# PFC_Method_AirSens_V1.net
KiCad netlist of a schematic drawn in EAGLE
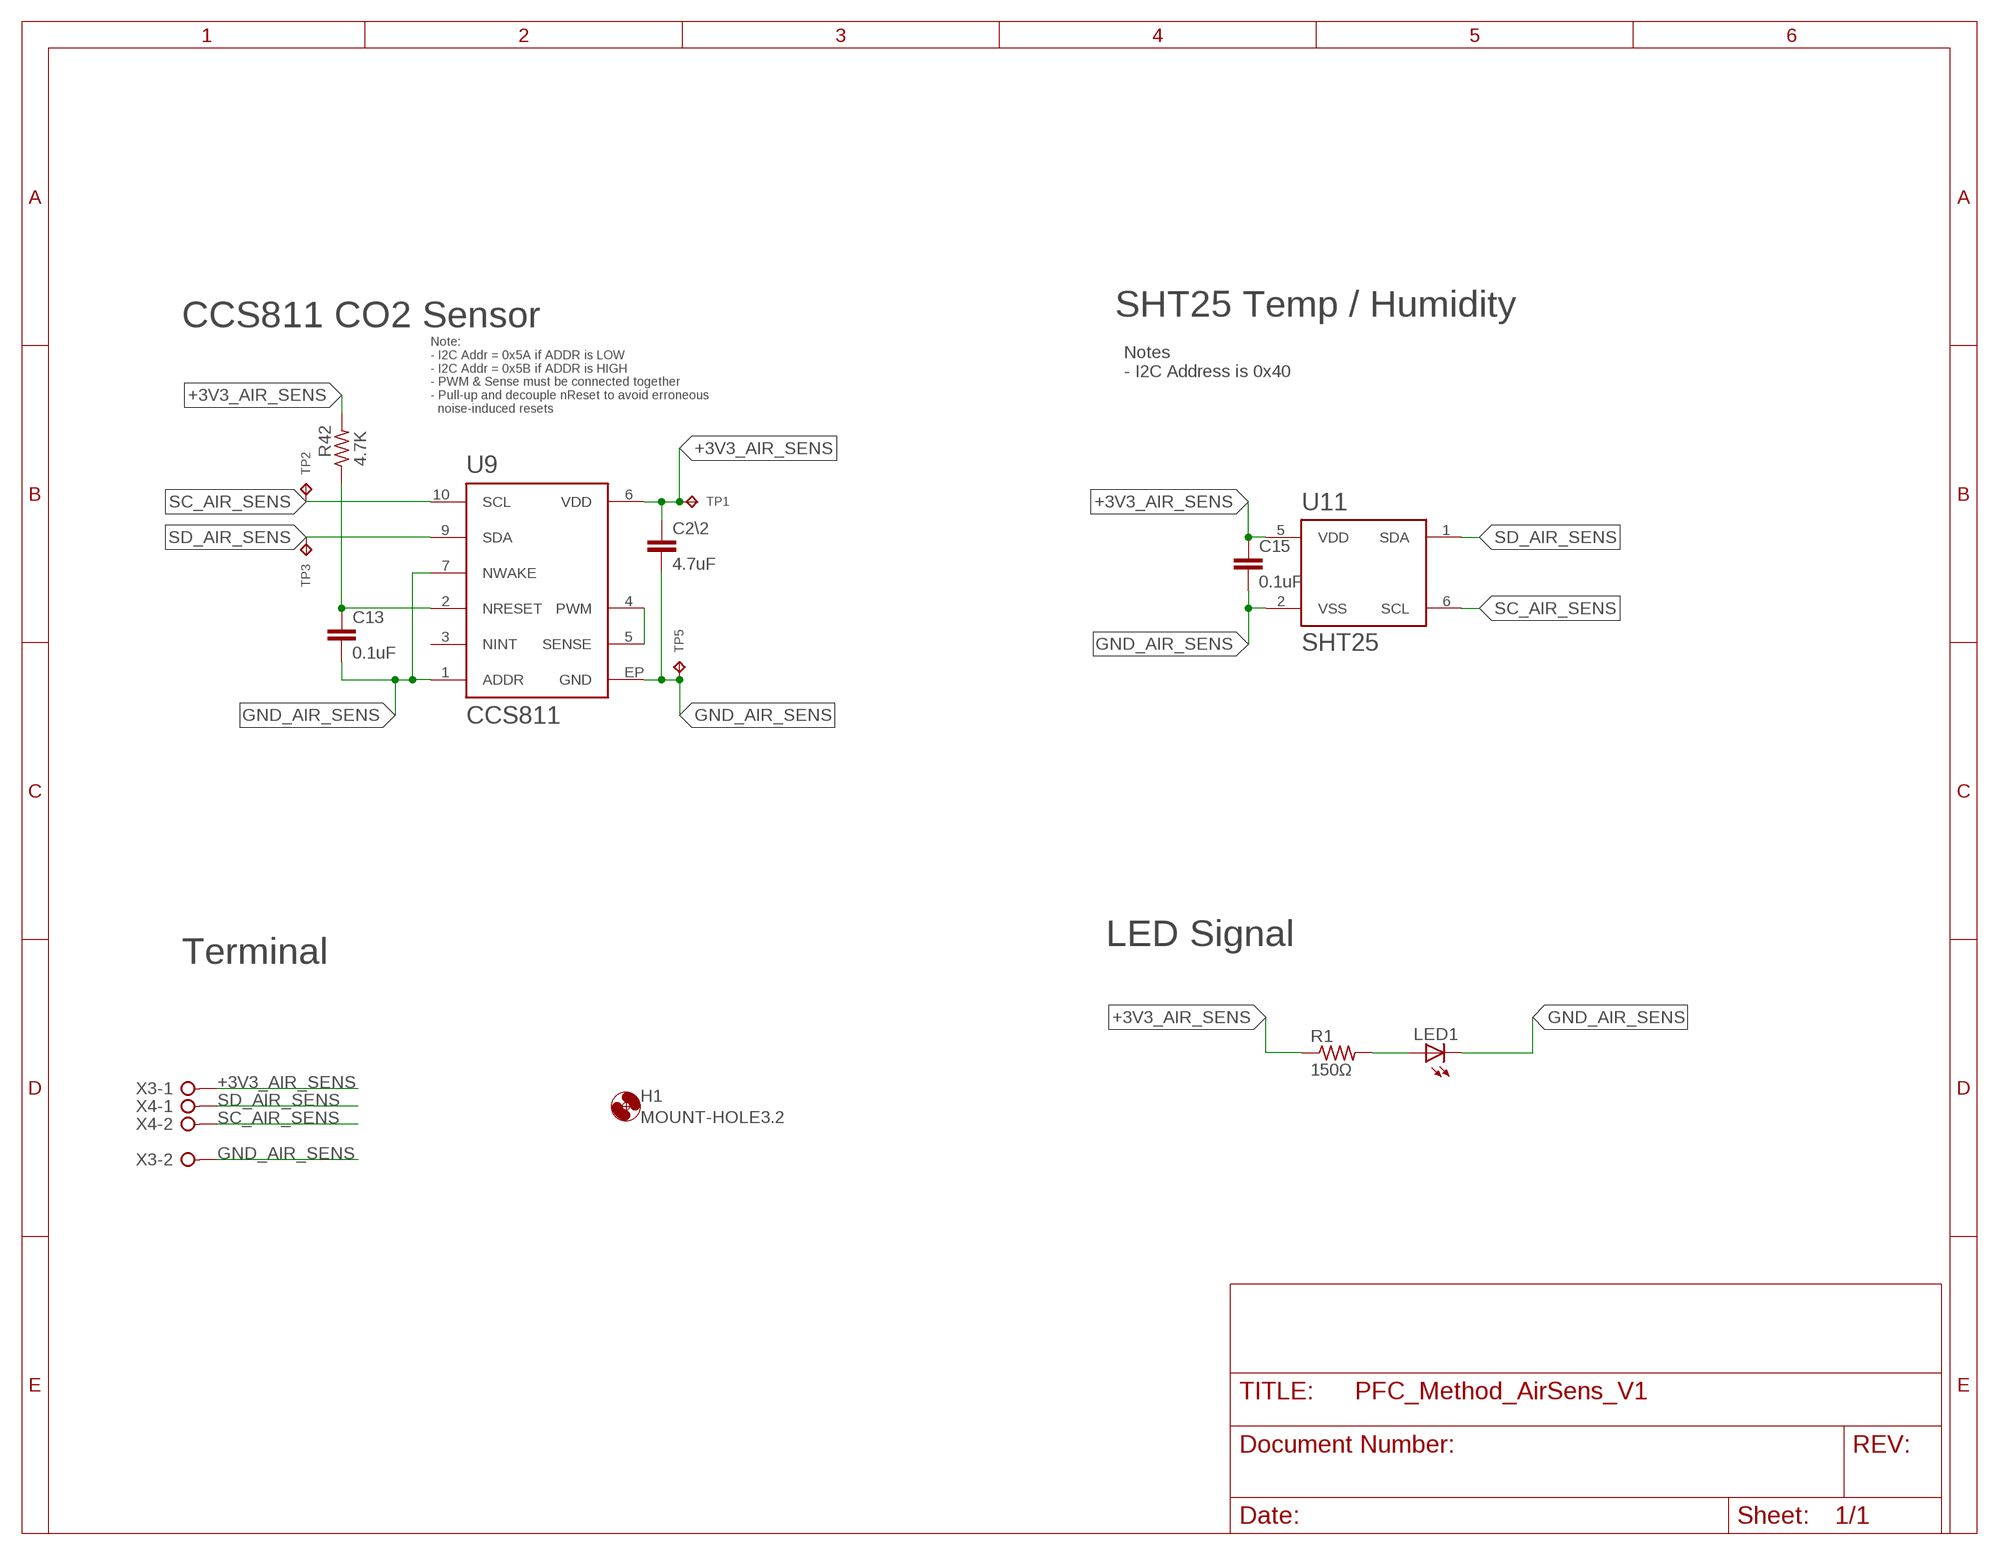
[diagram p0: schematic, sheet 1, part 1 of 2]
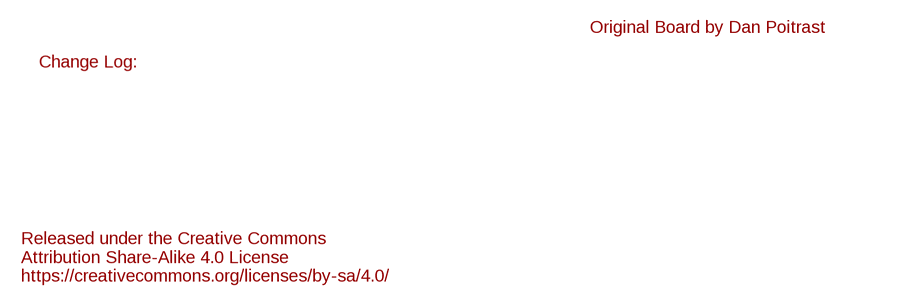
[diagram p1: schematic, sheet 1, part 2 of 2]

(export (version "E")
  (design (tool "Eeschema 10.0.6"))
  (components
    (comp (ref "C2\\2")
      (value "4.7uF")
      (footprint "eagle-import:C0805")
      (fields (field (name "MANUFACTURER") "Samsung") (field (name "MPN") "CL21A475KBQNNNE"))
      (libsource (lib "eagle-import") (part "4.7UF-CL21A475KBQNNNE"))
    )
    (comp (ref "C13")
      (value "0.1uF")
      (footprint "eagle-import:C0603")
      (fields (field (name "MANUFACTURER") "Kemet") (field (name "MPN") "C0603C104K5RACTU"))
      (libsource (lib "eagle-import") (part "0.1UF-C0603C104K5RACTU"))
    )
    (comp (ref "C15")
      (value "0.1uF")
      (footprint "eagle-import:C0603")
      (fields (field (name "MANUFACTURER") "Kemet") (field (name "MPN") "C0603C104K5RACTU"))
      (libsource (lib "eagle-import") (part "0.1UF-C0603C104K5RACTU"))
    )
    (comp (ref "H1")
      (value "MOUNT-HOLE3.2")
      (footprint "eagle-import:3,2")
      (libsource (lib "eagle-import") (part "MOUNT-HOLE3.2"))
    )
    (comp (ref "LED1")
      (value "LED5MM")
      (footprint "eagle-import:LED5MM")
      (libsource (lib "eagle-import") (part "LED5MM"))
    )
    (comp (ref "R1")
      (value "150Ω")
      (footprint "eagle-import:0207_10")
      (libsource (lib "eagle-import") (part "R-US_0207/10"))
    )
    (comp (ref "R42")
      (value "4.7K")
      (footprint "eagle-import:R1206")
      (fields (field (name "MANUFACTURER") "Yageo") (field (name "MPN") "RC1206JR-074K7L"))
      (libsource (lib "eagle-import") (part "4.7K-RC1206JR-074K7L"))
    )
    (comp (ref "TP1")
      (value "TPTP06R")
      (footprint "eagle-import:TP06R")
      (libsource (lib "eagle-import") (part "TPTP06R"))
    )
    (comp (ref "TP2")
      (value "TPTP06R")
      (footprint "eagle-import:TP06R")
      (libsource (lib "eagle-import") (part "TPTP06R"))
    )
    (comp (ref "TP3")
      (value "TPTP06R")
      (footprint "eagle-import:TP06R")
      (libsource (lib "eagle-import") (part "TPTP06R"))
    )
    (comp (ref "TP5")
      (value "TPTP06R")
      (footprint "eagle-import:TP06R")
      (libsource (lib "eagle-import") (part "TPTP06R"))
    )
    (comp (ref "U9")
      (value "CCS811")
      (footprint "eagle-import:CCS811")
      (fields (field (name "MANUFACTURER") "ams"))
      (libsource (lib "eagle-import") (part "CCS811"))
    )
    (comp (ref "U11")
      (value "SHT25")
      (footprint "eagle-import:SHT2X")
      (fields (field (name "MANUFACTURER") "Sensirion AG"))
      (libsource (lib "eagle-import") (part "SHT25"))
    )
    (comp (ref "X3")
      (value "W237-02P")
      (footprint "eagle-import:W237-132")
      (libsource (lib "eagle-import") (part "W237-02P"))
    )
    (comp (ref "X4")
      (value "W237-02P")
      (footprint "eagle-import:W237-132")
      (libsource (lib "eagle-import") (part "W237-02P"))
    )
  )
  (nets
    (net (code "1") (name "+3V3_AIR_SENS") (class "Default")
      (node (ref "C15") (pin "1") (pinfunction "1_1") (pintype "passive"))
      (node (ref "C2\\2") (pin "1") (pinfunction "1_1") (pintype "passive"))
      (node (ref "R1") (pin "1") (pinfunction "1_1") (pintype "passive"))
      (node (ref "R42") (pin "2") (pinfunction "2_2") (pintype "passive"))
      (node (ref "TP1") (pin "TP") (pinfunction "TP_TP") (pintype "input"))
      (node (ref "U11") (pin "5") (pinfunction "VDD_5") (pintype "power_in"))
      (node (ref "U9") (pin "6") (pinfunction "VDD_6") (pintype "power_in"))
      (node (ref "X3") (pin "1") (pinfunction "KL_1") (pintype "passive"))
    )
    (net (code "2") (name "GND_AIR_SENS") (class "Default")
      (node (ref "C13") (pin "2") (pinfunction "2_2") (pintype "passive"))
      (node (ref "C15") (pin "2") (pinfunction "2_2") (pintype "passive"))
      (node (ref "C2\\2") (pin "2") (pinfunction "2_2") (pintype "passive"))
      (node (ref "LED1") (pin "K") (pinfunction "C_K") (pintype "passive"))
      (node (ref "TP5") (pin "TP") (pinfunction "TP_TP") (pintype "input"))
      (node (ref "U11") (pin "2") (pinfunction "VSS_2") (pintype "power_in"))
      (node (ref "U9") (pin "1") (pinfunction "ADDR_1") (pintype "bidirectional"))
      (node (ref "U9") (pin "7") (pinfunction "NWAKE_7") (pintype "bidirectional"))
      (node (ref "U9") (pin "EP") (pinfunction "GND_EP") (pintype "power_in"))
      (node (ref "X3") (pin "2") (pinfunction "KL_2") (pintype "passive"))
    )
    (net (code "3") (name "Net-(LED1-PadA)") (class "Default")
      (node (ref "LED1") (pin "A") (pinfunction "A_A") (pintype "passive"))
      (node (ref "R1") (pin "2") (pinfunction "2_2") (pintype "passive"))
    )
    (net (code "4") (name "Net-(U9-NRESET)") (class "Default")
      (node (ref "C13") (pin "1") (pinfunction "1_1") (pintype "passive"))
      (node (ref "R42") (pin "1") (pinfunction "1_1") (pintype "passive"))
      (node (ref "U9") (pin "2") (pinfunction "NRESET_2") (pintype "bidirectional"))
    )
    (net (code "5") (name "Net-(U9-PWM)") (class "Default")
      (node (ref "U9") (pin "4") (pinfunction "PWM_4") (pintype "bidirectional"))
      (node (ref "U9") (pin "5") (pinfunction "SENSE_5") (pintype "bidirectional"))
    )
    (net (code "6") (name "SC_AIR_SENS") (class "Default")
      (node (ref "TP2") (pin "TP") (pinfunction "TP_TP") (pintype "input"))
      (node (ref "U11") (pin "6") (pinfunction "SCL_6") (pintype "bidirectional"))
      (node (ref "U9") (pin "10") (pinfunction "SCL_10") (pintype "bidirectional"))
      (node (ref "X4") (pin "2") (pinfunction "KL_2") (pintype "passive"))
    )
    (net (code "7") (name "SD_AIR_SENS") (class "Default")
      (node (ref "TP3") (pin "TP") (pinfunction "TP_TP") (pintype "input"))
      (node (ref "U11") (pin "1") (pinfunction "SDA_1") (pintype "bidirectional"))
      (node (ref "U9") (pin "9") (pinfunction "SDA_9") (pintype "bidirectional"))
      (node (ref "X4") (pin "1") (pinfunction "KL_1") (pintype "passive"))
    )
    (net (code "8") (name "unconnected-(U9-NINT-Pad3)") (class "Default")
      (node (ref "U9") (pin "3") (pinfunction "NINT_3") (pintype "bidirectional"))
    )
  )
)
